# digitboard.net
KiCad netlist of a schematic drawn in EAGLE
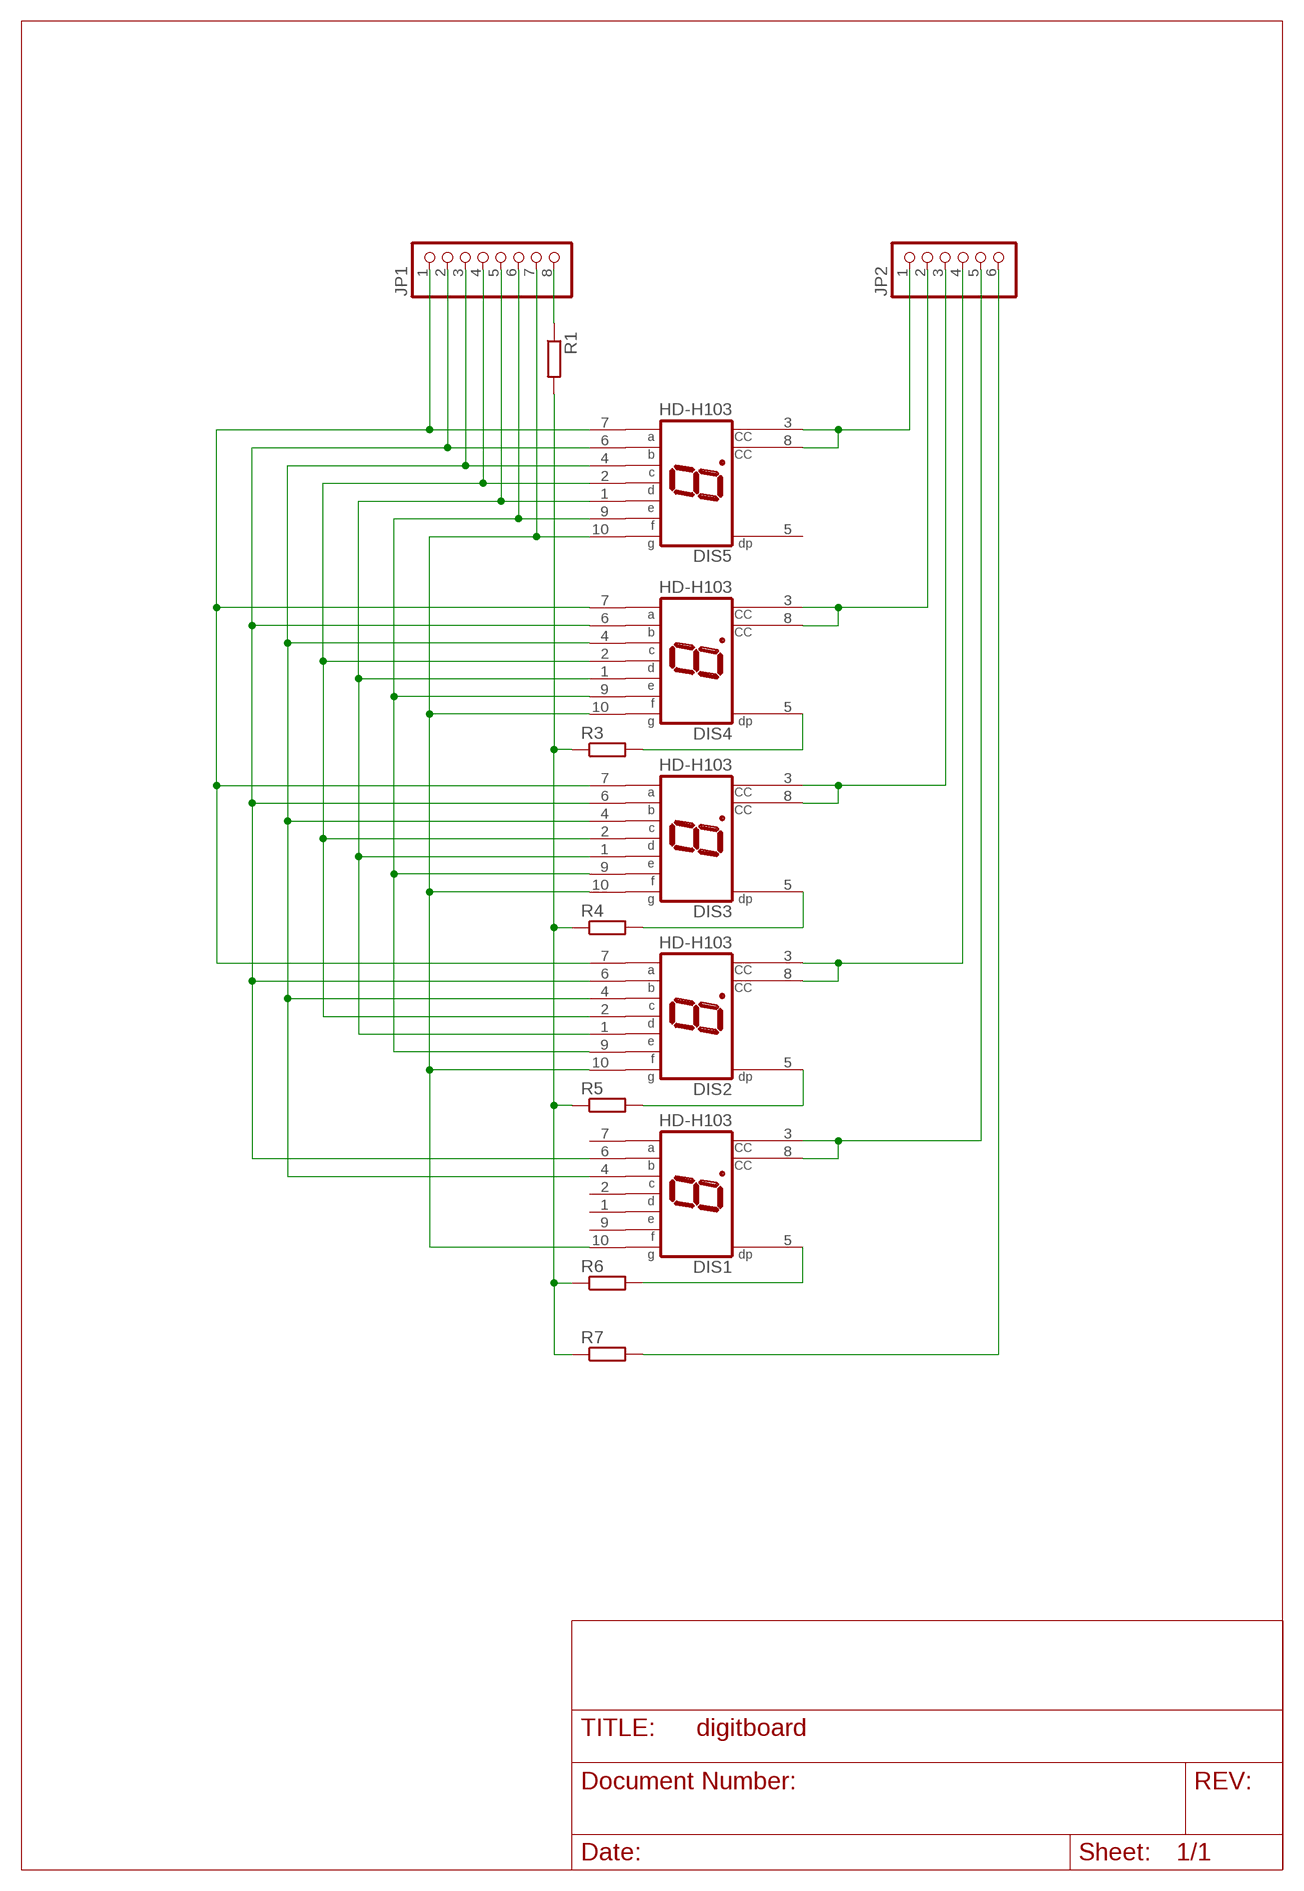
[diagram p0: schematic, sheet 1]

(export (version "E")
  (design (tool "Eeschema 10.0.6"))
  (components
    (comp (ref "DIS1")
      (value "HD-H103")
      (footprint "eagle-import:HDSP-M")
      (libsource (lib "eagle-import") (part "HD-H103"))
    )
    (comp (ref "DIS2")
      (value "HD-H103")
      (footprint "eagle-import:HDSP-M")
      (libsource (lib "eagle-import") (part "HD-H103"))
    )
    (comp (ref "DIS3")
      (value "HD-H103")
      (footprint "eagle-import:HDSP-M")
      (libsource (lib "eagle-import") (part "HD-H103"))
    )
    (comp (ref "DIS4")
      (value "HD-H103")
      (footprint "eagle-import:HDSP-M")
      (libsource (lib "eagle-import") (part "HD-H103"))
    )
    (comp (ref "DIS5")
      (value "HD-H103")
      (footprint "eagle-import:HDSP-M")
      (libsource (lib "eagle-import") (part "HD-H103"))
    )
    (comp (ref "JP1")
      (value "PINHD-1X8")
      (footprint "eagle-import:1X08")
      (libsource (lib "eagle-import") (part "PINHD-1X8"))
    )
    (comp (ref "JP2")
      (value "PINHD-1X6")
      (footprint "eagle-import:1X06")
      (libsource (lib "eagle-import") (part "PINHD-1X6"))
    )
    (comp (ref "R1")
      (value "R-EU_R0603")
      (footprint "eagle-import:R0603")
      (libsource (lib "eagle-import") (part "R-EU_R0603"))
    )
    (comp (ref "R3")
      (value "R-EU_R0603")
      (footprint "eagle-import:R0603")
      (libsource (lib "eagle-import") (part "R-EU_R0603"))
    )
    (comp (ref "R4")
      (value "R-EU_R0603")
      (footprint "eagle-import:R0603")
      (libsource (lib "eagle-import") (part "R-EU_R0603"))
    )
    (comp (ref "R5")
      (value "R-EU_R0603")
      (footprint "eagle-import:R0603")
      (libsource (lib "eagle-import") (part "R-EU_R0603"))
    )
    (comp (ref "R6")
      (value "R-EU_R0603")
      (footprint "eagle-import:R0603")
      (libsource (lib "eagle-import") (part "R-EU_R0603"))
    )
    (comp (ref "R7")
      (value "R-EU_R0603")
      (footprint "eagle-import:R0603")
      (libsource (lib "eagle-import") (part "R-EU_R0603"))
    )
  )
  (nets
    (net (code "1") (name "Net-(DIS1-B)") (class "Default")
      (node (ref "DIS1") (pin "6") (pinfunction "B_6") (pintype "passive"))
      (node (ref "DIS2") (pin "6") (pinfunction "B_6") (pintype "passive"))
      (node (ref "DIS3") (pin "6") (pinfunction "B_6") (pintype "passive"))
      (node (ref "DIS4") (pin "6") (pinfunction "B_6") (pintype "passive"))
      (node (ref "DIS5") (pin "6") (pinfunction "B_6") (pintype "passive"))
      (node (ref "JP1") (pin "2") (pinfunction "2_2") (pintype "passive"))
    )
    (net (code "2") (name "Net-(DIS1-C)") (class "Default")
      (node (ref "DIS1") (pin "4") (pinfunction "C_4") (pintype "passive"))
      (node (ref "DIS2") (pin "4") (pinfunction "C_4") (pintype "passive"))
      (node (ref "DIS3") (pin "4") (pinfunction "C_4") (pintype "passive"))
      (node (ref "DIS4") (pin "4") (pinfunction "C_4") (pintype "passive"))
      (node (ref "DIS5") (pin "4") (pinfunction "C_4") (pintype "passive"))
      (node (ref "JP1") (pin "3") (pinfunction "3_3") (pintype "passive"))
    )
    (net (code "3") (name "Net-(DIS1-CC-Pad3)") (class "Default")
      (node (ref "DIS1") (pin "3") (pinfunction "CC_3") (pintype "passive"))
      (node (ref "DIS1") (pin "8") (pinfunction "CC_8") (pintype "passive"))
      (node (ref "JP2") (pin "5") (pinfunction "5_5") (pintype "passive"))
    )
    (net (code "4") (name "Net-(DIS1-DP)") (class "Default")
      (node (ref "DIS1") (pin "5") (pinfunction "DP_5") (pintype "passive"))
      (node (ref "R6") (pin "2") (pinfunction "2_2") (pintype "passive"))
    )
    (net (code "5") (name "Net-(DIS1-G)") (class "Default")
      (node (ref "DIS1") (pin "10") (pinfunction "G_10") (pintype "passive"))
      (node (ref "DIS2") (pin "10") (pinfunction "G_10") (pintype "passive"))
      (node (ref "DIS3") (pin "10") (pinfunction "G_10") (pintype "passive"))
      (node (ref "DIS4") (pin "10") (pinfunction "G_10") (pintype "passive"))
      (node (ref "DIS5") (pin "10") (pinfunction "G_10") (pintype "passive"))
      (node (ref "JP1") (pin "7") (pinfunction "7_7") (pintype "passive"))
    )
    (net (code "6") (name "Net-(DIS2-A)") (class "Default")
      (node (ref "DIS2") (pin "7") (pinfunction "A_7") (pintype "passive"))
      (node (ref "DIS3") (pin "7") (pinfunction "A_7") (pintype "passive"))
      (node (ref "DIS4") (pin "7") (pinfunction "A_7") (pintype "passive"))
      (node (ref "DIS5") (pin "7") (pinfunction "A_7") (pintype "passive"))
      (node (ref "JP1") (pin "1") (pinfunction "1_1") (pintype "passive"))
    )
    (net (code "7") (name "Net-(DIS2-CC-Pad3)") (class "Default")
      (node (ref "DIS2") (pin "3") (pinfunction "CC_3") (pintype "passive"))
      (node (ref "DIS2") (pin "8") (pinfunction "CC_8") (pintype "passive"))
      (node (ref "JP2") (pin "4") (pinfunction "4_4") (pintype "passive"))
    )
    (net (code "8") (name "Net-(DIS2-D)") (class "Default")
      (node (ref "DIS2") (pin "2") (pinfunction "D_2") (pintype "passive"))
      (node (ref "DIS3") (pin "2") (pinfunction "D_2") (pintype "passive"))
      (node (ref "DIS4") (pin "2") (pinfunction "D_2") (pintype "passive"))
      (node (ref "DIS5") (pin "2") (pinfunction "D_2") (pintype "passive"))
      (node (ref "JP1") (pin "4") (pinfunction "4_4") (pintype "passive"))
    )
    (net (code "9") (name "Net-(DIS2-DP)") (class "Default")
      (node (ref "DIS2") (pin "5") (pinfunction "DP_5") (pintype "passive"))
      (node (ref "R5") (pin "2") (pinfunction "2_2") (pintype "passive"))
    )
    (net (code "10") (name "Net-(DIS2-E)") (class "Default")
      (node (ref "DIS2") (pin "1") (pinfunction "E_1") (pintype "passive"))
      (node (ref "DIS3") (pin "1") (pinfunction "E_1") (pintype "passive"))
      (node (ref "DIS4") (pin "1") (pinfunction "E_1") (pintype "passive"))
      (node (ref "DIS5") (pin "1") (pinfunction "E_1") (pintype "passive"))
      (node (ref "JP1") (pin "5") (pinfunction "5_5") (pintype "passive"))
    )
    (net (code "11") (name "Net-(DIS2-F)") (class "Default")
      (node (ref "DIS2") (pin "9") (pinfunction "F_9") (pintype "passive"))
      (node (ref "DIS3") (pin "9") (pinfunction "F_9") (pintype "passive"))
      (node (ref "DIS4") (pin "9") (pinfunction "F_9") (pintype "passive"))
      (node (ref "DIS5") (pin "9") (pinfunction "F_9") (pintype "passive"))
      (node (ref "JP1") (pin "6") (pinfunction "6_6") (pintype "passive"))
    )
    (net (code "12") (name "Net-(DIS3-CC-Pad3)") (class "Default")
      (node (ref "DIS3") (pin "3") (pinfunction "CC_3") (pintype "passive"))
      (node (ref "DIS3") (pin "8") (pinfunction "CC_8") (pintype "passive"))
      (node (ref "JP2") (pin "3") (pinfunction "3_3") (pintype "passive"))
    )
    (net (code "13") (name "Net-(DIS3-DP)") (class "Default")
      (node (ref "DIS3") (pin "5") (pinfunction "DP_5") (pintype "passive"))
      (node (ref "R4") (pin "2") (pinfunction "2_2") (pintype "passive"))
    )
    (net (code "14") (name "Net-(DIS4-CC-Pad3)") (class "Default")
      (node (ref "DIS4") (pin "3") (pinfunction "CC_3") (pintype "passive"))
      (node (ref "DIS4") (pin "8") (pinfunction "CC_8") (pintype "passive"))
      (node (ref "JP2") (pin "2") (pinfunction "2_2") (pintype "passive"))
    )
    (net (code "15") (name "Net-(DIS4-DP)") (class "Default")
      (node (ref "DIS4") (pin "5") (pinfunction "DP_5") (pintype "passive"))
      (node (ref "R3") (pin "2") (pinfunction "2_2") (pintype "passive"))
    )
    (net (code "16") (name "Net-(DIS5-CC-Pad3)") (class "Default")
      (node (ref "DIS5") (pin "3") (pinfunction "CC_3") (pintype "passive"))
      (node (ref "DIS5") (pin "8") (pinfunction "CC_8") (pintype "passive"))
      (node (ref "JP2") (pin "1") (pinfunction "1_1") (pintype "passive"))
    )
    (net (code "17") (name "Net-(JP1-Pad8)") (class "Default")
      (node (ref "JP1") (pin "8") (pinfunction "8_8") (pintype "passive"))
      (node (ref "R1") (pin "1") (pinfunction "1_1") (pintype "passive"))
    )
    (net (code "18") (name "Net-(JP2-Pad6)") (class "Default")
      (node (ref "JP2") (pin "6") (pinfunction "6_6") (pintype "passive"))
      (node (ref "R7") (pin "2") (pinfunction "2_2") (pintype "passive"))
    )
    (net (code "19") (name "Net-(R1-Pad2)") (class "Default")
      (node (ref "R1") (pin "2") (pinfunction "2_2") (pintype "passive"))
      (node (ref "R3") (pin "1") (pinfunction "1_1") (pintype "passive"))
      (node (ref "R4") (pin "1") (pinfunction "1_1") (pintype "passive"))
      (node (ref "R5") (pin "1") (pinfunction "1_1") (pintype "passive"))
      (node (ref "R6") (pin "1") (pinfunction "1_1") (pintype "passive"))
      (node (ref "R7") (pin "1") (pinfunction "1_1") (pintype "passive"))
    )
    (net (code "20") (name "unconnected-(DIS1-A-Pad7)") (class "Default")
      (node (ref "DIS1") (pin "7") (pinfunction "A_7") (pintype "passive"))
    )
    (net (code "21") (name "unconnected-(DIS1-D-Pad2)") (class "Default")
      (node (ref "DIS1") (pin "2") (pinfunction "D_2") (pintype "passive"))
    )
    (net (code "22") (name "unconnected-(DIS1-E-Pad1)") (class "Default")
      (node (ref "DIS1") (pin "1") (pinfunction "E_1") (pintype "passive"))
    )
    (net (code "23") (name "unconnected-(DIS1-F-Pad9)") (class "Default")
      (node (ref "DIS1") (pin "9") (pinfunction "F_9") (pintype "passive"))
    )
    (net (code "24") (name "unconnected-(DIS5-DP-Pad5)") (class "Default")
      (node (ref "DIS5") (pin "5") (pinfunction "DP_5") (pintype "passive"))
    )
  )
)
